# 404_Schematic.net
KiCad netlist of a schematic drawn in Altium Designer
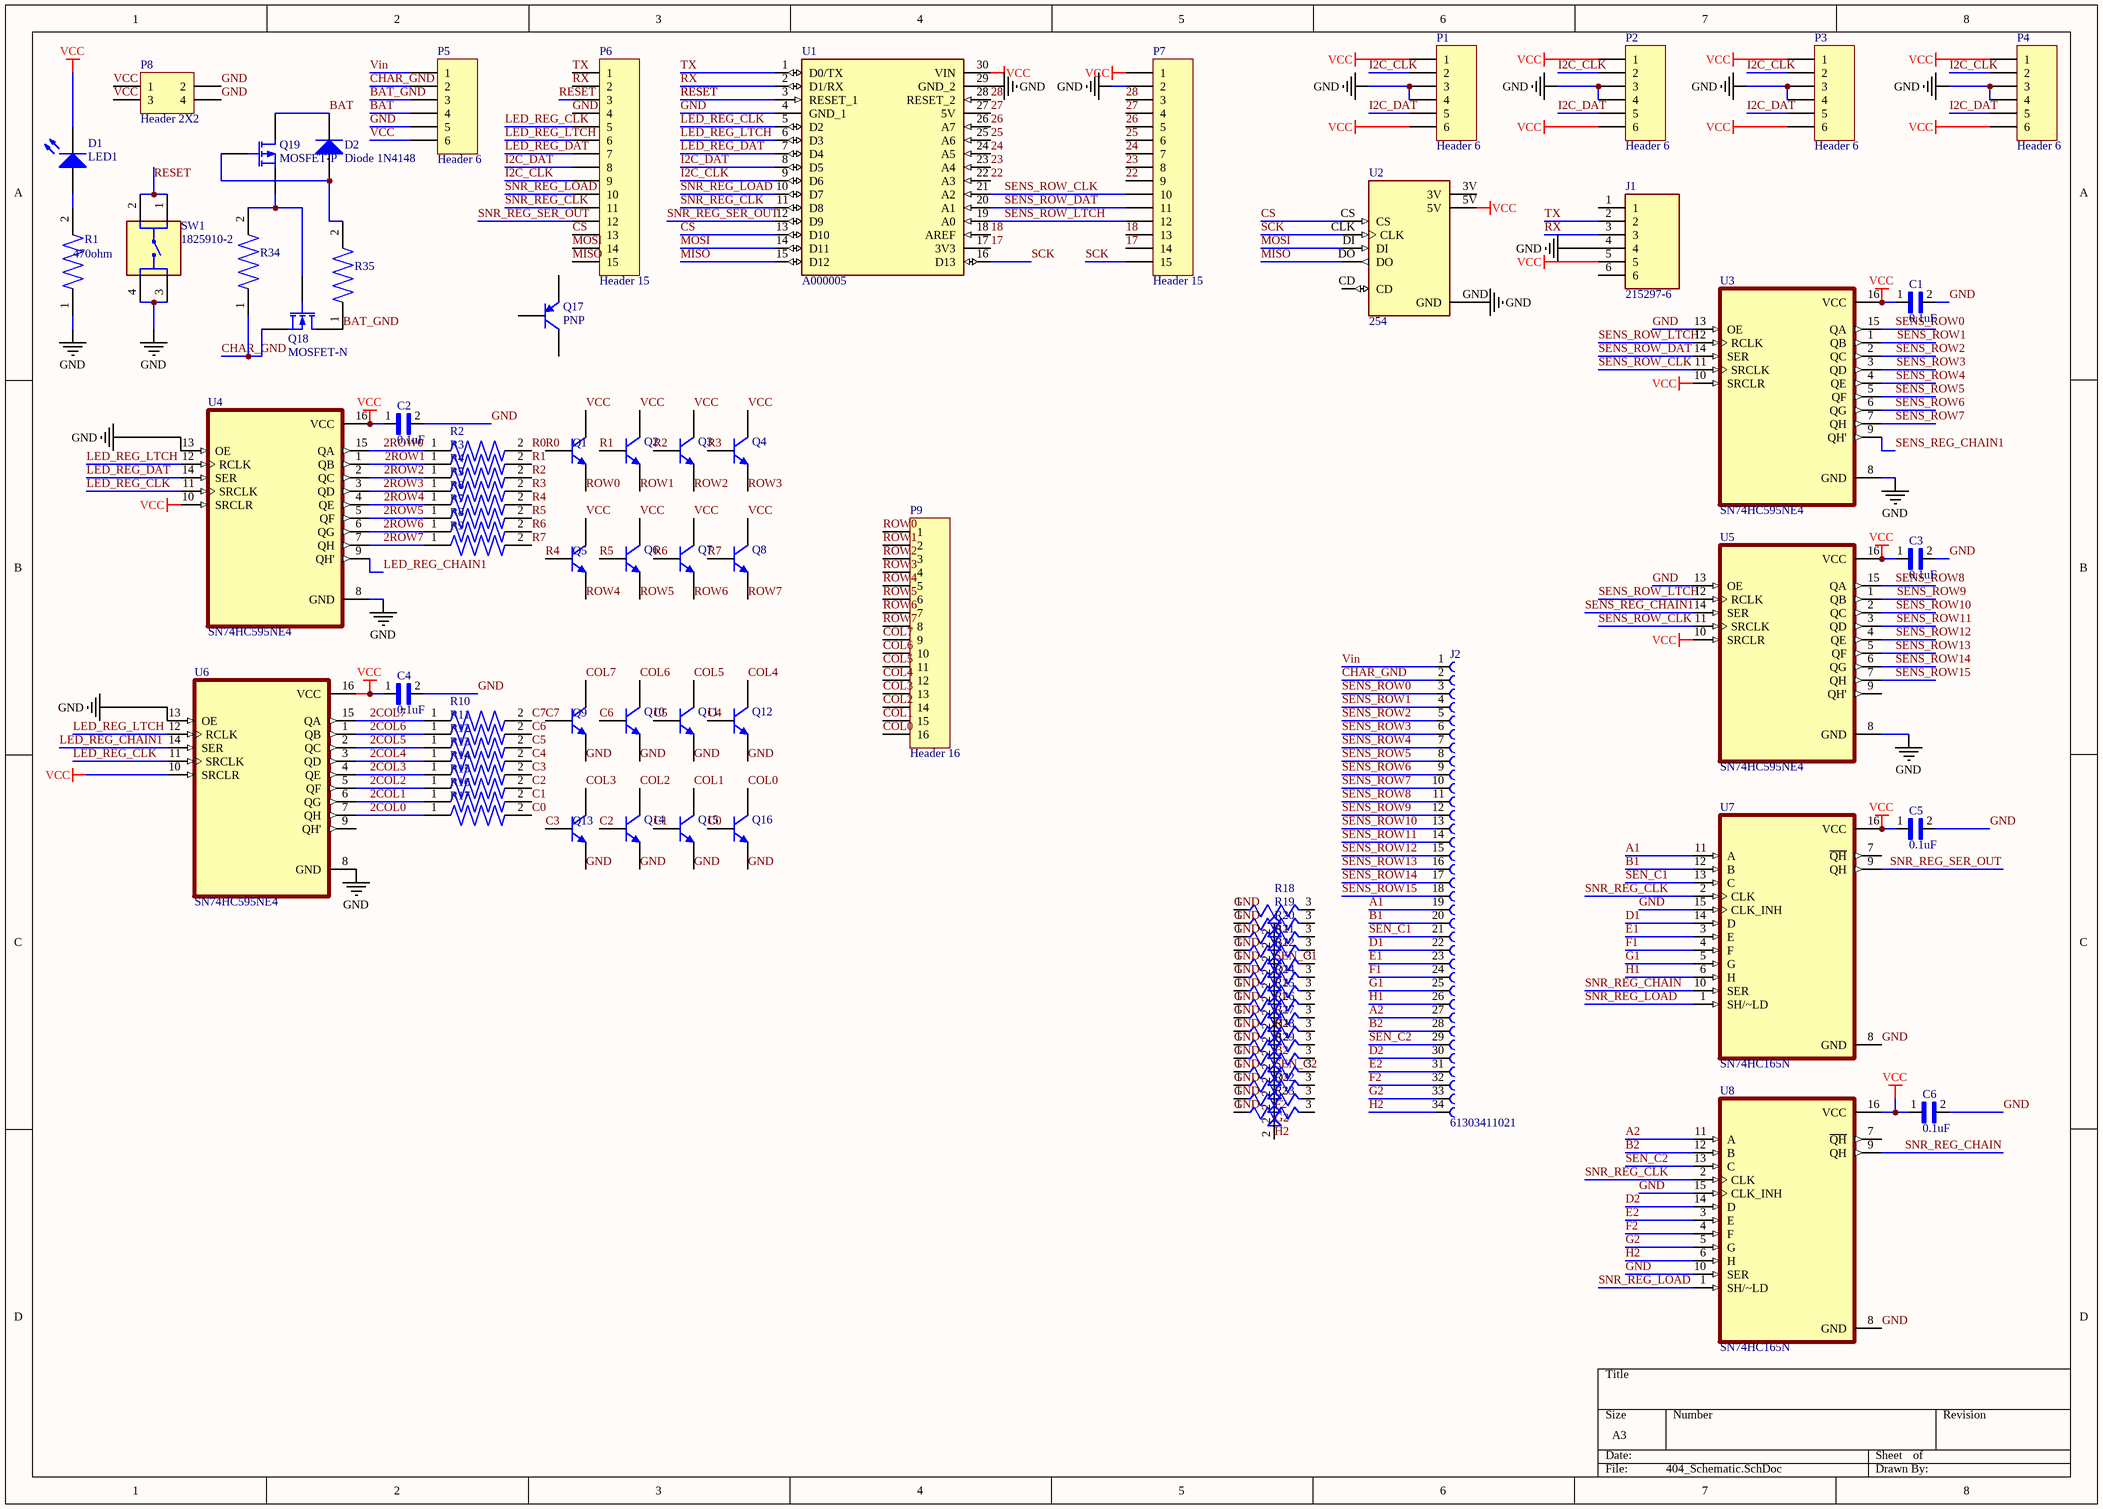
[diagram p0: 404_Schematic.SchDoc]

(export (version "E")
  (design (tool "Eeschema 10.0.6"))
  (components
    (comp (ref "C1")
      (value "0.1uF")
      (footprint "CAP_RDER72H103K1K1H03B")
      (description "Cap Ceramic 0.0047uF 50V C0G 5% Radial 5mm 125C Bulk")
      (fields (field (name "MP") "RDER72H103K1K1H03B") (field (name "MF") "{'manufacturer': u'Murata'}"))
      (libsource (lib "SnapEDA_Library") (part "RDER72H103K1K1H03B"))
    )
    (comp (ref "C2")
      (value "0.1uF")
      (footprint "CAP_RDER72H103K1K1H03B")
      (description "Cap Ceramic 0.0047uF 50V C0G 5% Radial 5mm 125C Bulk")
      (fields (field (name "MP") "RDER72H103K1K1H03B") (field (name "MF") "{'manufacturer': u'Murata'}"))
      (libsource (lib "SnapEDA_Library") (part "RDER72H103K1K1H03B"))
    )
    (comp (ref "C3")
      (value "0.1uF")
      (footprint "CAP_RDER72H103K1K1H03B")
      (description "Cap Ceramic 0.0047uF 50V C0G 5% Radial 5mm 125C Bulk")
      (fields (field (name "MP") "RDER72H103K1K1H03B") (field (name "MF") "{'manufacturer': u'Murata'}"))
      (libsource (lib "SnapEDA_Library") (part "RDER72H103K1K1H03B"))
    )
    (comp (ref "C4")
      (value "0.1uF")
      (footprint "CAP_RDER72H103K1K1H03B")
      (description "Cap Ceramic 0.0047uF 50V C0G 5% Radial 5mm 125C Bulk")
      (fields (field (name "MP") "RDER72H103K1K1H03B") (field (name "MF") "{'manufacturer': u'Murata'}"))
      (libsource (lib "SnapEDA_Library") (part "RDER72H103K1K1H03B"))
    )
    (comp (ref "C5")
      (value "0.1uF")
      (footprint "CAP_RDER72H103K1K1H03B")
      (description "Cap Ceramic 0.0047uF 50V C0G 5% Radial 5mm 125C Bulk")
      (fields (field (name "MP") "RDER72H103K1K1H03B") (field (name "MF") "{'manufacturer': u'Murata'}"))
      (libsource (lib "SnapEDA_Library") (part "RDER72H103K1K1H03B"))
    )
    (comp (ref "C6")
      (value "0.1uF")
      (footprint "CAP_RDER72H103K1K1H03B")
      (description "Cap Ceramic 0.0047uF 50V C0G 5% Radial 5mm 125C Bulk")
      (fields (field (name "MP") "RDER72H103K1K1H03B") (field (name "MF") "{'manufacturer': u'Murata'}"))
      (libsource (lib "SnapEDA_Library") (part "RDER72H103K1K1H03B"))
    )
    (comp (ref "D1")
      (value "LED1")
      (footprint "LED-1")
      (description "Typical RED GaAs LED")
      (fields (field (name "PUBLISHER") "Altium Limited"))
      (libsource (lib "Miscellaneous Devices") (part "LED1"))
    )
    (comp (ref "D2")
      (value "Diode 1N4148")
      (footprint "DO-35")
      (description "High Conductance Fast Diode")
      (fields (field (name "PUBLISHER") "Altium Limited"))
      (libsource (lib "Miscellaneous Devices") (part "Diode 1N4148"))
    )
    (comp (ref "J1")
      (value "215297-6")
      (footprint "TE_215297-6")
      (fields (field (name "MF") "{'manufacturer': u'TE Connectivity'}"))
      (libsource (lib "SnapEDA_Library") (part "215297-6"))
    )
    (comp (ref "J2")
      (value "61303411021")
      (footprint "61303411021:61303411021")
      (fields (field (name "MF") "{'manufacturer': u'~{W}xfcrth Elektronik'}"))
      (libsource (lib "*") (part "61303411021"))
    )
    (comp (ref "P1")
      (value "Header 6")
      (footprint "HDR1X6")
      (description "Header, 6-Pin")
      (fields (field (name "PUBLISHER") "Altium Limited"))
      (libsource (lib "Miscellaneous Connectors") (part "Header 6"))
    )
    (comp (ref "P2")
      (value "Header 6")
      (footprint "HDR1X6")
      (description "Header, 6-Pin")
      (fields (field (name "PUBLISHER") "Altium Limited"))
      (libsource (lib "Miscellaneous Connectors") (part "Header 6"))
    )
    (comp (ref "P3")
      (value "Header 6")
      (footprint "HDR1X6")
      (description "Header, 6-Pin")
      (fields (field (name "PUBLISHER") "Altium Limited"))
      (libsource (lib "Miscellaneous Connectors") (part "Header 6"))
    )
    (comp (ref "P4")
      (value "Header 6")
      (footprint "HDR1X6")
      (description "Header, 6-Pin")
      (fields (field (name "PUBLISHER") "Altium Limited"))
      (libsource (lib "Miscellaneous Connectors") (part "Header 6"))
    )
    (comp (ref "P5")
      (value "Header 6")
      (footprint "HDR1X6")
      (description "Header, 6-Pin")
      (fields (field (name "PUBLISHER") "Altium Limited"))
      (libsource (lib "Miscellaneous Connectors") (part "Header 6"))
    )
    (comp (ref "P6")
      (value "Header 15")
      (footprint "HDR1X15")
      (description "Header, 15-Pin")
      (fields (field (name "PUBLISHER") "Altium Limited"))
      (libsource (lib "Miscellaneous Connectors") (part "Header 15"))
    )
    (comp (ref "P7")
      (value "Header 15")
      (footprint "HDR1X15")
      (description "Header, 15-Pin")
      (fields (field (name "PUBLISHER") "Altium Limited"))
      (libsource (lib "Miscellaneous Connectors") (part "Header 15"))
    )
    (comp (ref "P8")
      (value "Header 2X2")
      (footprint "HDR2X2")
      (description "Header, 2-Pin, Dual row")
      (fields (field (name "PUBLISHER") "Altium Limited"))
      (libsource (lib "Miscellaneous Connectors") (part "Header 2X2"))
    )
    (comp (ref "P9")
      (value "Header 16")
      (footprint "HDR1X16")
      (description "Header, 16-Pin")
      (fields (field (name "PUBLISHER") "Altium Limited"))
      (libsource (lib "Miscellaneous Connectors") (part "Header 16"))
    )
    (comp (ref "Q1")
      (value "2N3904")
      (footprint "TO-92A")
      (description "NPN General Purpose Amplifier")
      (fields (field (name "PUBLISHER") "Altium Limited"))
      (libsource (lib "Miscellaneous Devices") (part "2N3904"))
    )
    (comp (ref "Q2")
      (value "2N3904")
      (footprint "TO-92A")
      (description "NPN General Purpose Amplifier")
      (fields (field (name "PUBLISHER") "Altium Limited"))
      (libsource (lib "Miscellaneous Devices") (part "2N3904"))
    )
    (comp (ref "Q3")
      (value "2N3904")
      (footprint "TO-92A")
      (description "NPN General Purpose Amplifier")
      (fields (field (name "PUBLISHER") "Altium Limited"))
      (libsource (lib "Miscellaneous Devices") (part "2N3904"))
    )
    (comp (ref "Q4")
      (value "2N3904")
      (footprint "TO-92A")
      (description "NPN General Purpose Amplifier")
      (fields (field (name "PUBLISHER") "Altium Limited"))
      (libsource (lib "Miscellaneous Devices") (part "2N3904"))
    )
    (comp (ref "Q5")
      (value "2N3904")
      (footprint "TO-92A")
      (description "NPN General Purpose Amplifier")
      (fields (field (name "PUBLISHER") "Altium Limited"))
      (libsource (lib "Miscellaneous Devices") (part "2N3904"))
    )
    (comp (ref "Q6")
      (value "2N3904")
      (footprint "TO-92A")
      (description "NPN General Purpose Amplifier")
      (fields (field (name "PUBLISHER") "Altium Limited"))
      (libsource (lib "Miscellaneous Devices") (part "2N3904"))
    )
    (comp (ref "Q7")
      (value "2N3904")
      (footprint "TO-92A")
      (description "NPN General Purpose Amplifier")
      (fields (field (name "PUBLISHER") "Altium Limited"))
      (libsource (lib "Miscellaneous Devices") (part "2N3904"))
    )
    (comp (ref "Q8")
      (value "2N3904")
      (footprint "TO-92A")
      (description "NPN General Purpose Amplifier")
      (fields (field (name "PUBLISHER") "Altium Limited"))
      (libsource (lib "Miscellaneous Devices") (part "2N3904"))
    )
    (comp (ref "Q9")
      (value "2N3904")
      (footprint "TO-92A")
      (description "NPN General Purpose Amplifier")
      (fields (field (name "PUBLISHER") "Altium Limited"))
      (libsource (lib "Miscellaneous Devices") (part "2N3904"))
    )
    (comp (ref "Q10")
      (value "2N3904")
      (footprint "TO-92A")
      (description "NPN General Purpose Amplifier")
      (fields (field (name "PUBLISHER") "Altium Limited"))
      (libsource (lib "Miscellaneous Devices") (part "2N3904"))
    )
    (comp (ref "Q11")
      (value "2N3904")
      (footprint "TO-92A")
      (description "NPN General Purpose Amplifier")
      (fields (field (name "PUBLISHER") "Altium Limited"))
      (libsource (lib "Miscellaneous Devices") (part "2N3904"))
    )
    (comp (ref "Q12")
      (value "2N3904")
      (footprint "TO-92A")
      (description "NPN General Purpose Amplifier")
      (fields (field (name "PUBLISHER") "Altium Limited"))
      (libsource (lib "Miscellaneous Devices") (part "2N3904"))
    )
    (comp (ref "Q13")
      (value "2N3904")
      (footprint "TO-92A")
      (description "NPN General Purpose Amplifier")
      (fields (field (name "PUBLISHER") "Altium Limited"))
      (libsource (lib "Miscellaneous Devices") (part "2N3904"))
    )
    (comp (ref "Q14")
      (value "2N3904")
      (footprint "TO-92A")
      (description "NPN General Purpose Amplifier")
      (fields (field (name "PUBLISHER") "Altium Limited"))
      (libsource (lib "Miscellaneous Devices") (part "2N3904"))
    )
    (comp (ref "Q15")
      (value "2N3904")
      (footprint "TO-92A")
      (description "NPN General Purpose Amplifier")
      (fields (field (name "PUBLISHER") "Altium Limited"))
      (libsource (lib "Miscellaneous Devices") (part "2N3904"))
    )
    (comp (ref "Q16")
      (value "2N3904")
      (footprint "TO-92A")
      (description "NPN General Purpose Amplifier")
      (fields (field (name "PUBLISHER") "Altium Limited"))
      (libsource (lib "Miscellaneous Devices") (part "2N3904"))
    )
    (comp (ref "Q17")
      (value "PNP")
      (footprint "SOT-23B_N")
      (description "PNP Bipolar Transistor")
      (fields (field (name "PUBLISHER") "Altium Limited"))
      (libsource (lib "Miscellaneous Devices") (part "PNP"))
    )
    (comp (ref "Q18")
      (value "MOSFET-N")
      (footprint "E3")
      (description "N-Channel MOSFET")
      (fields (field (name "PUBLISHER") "Altium Limited"))
      (libsource (lib "Miscellaneous Devices") (part "MOSFET-N"))
    )
    (comp (ref "Q19")
      (value "MOSFET-P")
      (footprint "E3")
      (description "P-Channel MOSFET")
      (fields (field (name "PUBLISHER") "Altium Limited"))
      (libsource (lib "Miscellaneous Devices") (part "MOSFET-P"))
    )
    (comp (ref "R1")
      (value "470ohm")
      (footprint "2-1623928-5:RESAD700W45L350D185")
      (description "CFR16 5% 10K 470 ohm")
      (fields (field (name "MP") "2-1623928-5") (field (name "MF") "{'manufacturer': u'TE Connectivity'}"))
      (libsource (lib "*") (part "2-1623928-5"))
    )
    (comp (ref "R2")
      (value "390")
      (footprint "RESAD700W45L350D185")
      (description "CFR16 5% 10K")
      (fields (field (name "MF") "{'manufacturer': u'TE Connectivity'}") (field (name "MP") "1-1623928-1"))
      (libsource (lib "SnapEDA_Library") (part "1-1623928-1"))
    )
    (comp (ref "R3")
      (value "390")
      (footprint "RESAD700W45L350D185")
      (description "CFR16 5% 10K")
      (fields (field (name "MF") "{'manufacturer': u'TE Connectivity'}") (field (name "MP") "1-1623928-1"))
      (libsource (lib "SnapEDA_Library") (part "1-1623928-1"))
    )
    (comp (ref "R4")
      (value "390")
      (footprint "RESAD700W45L350D185")
      (description "CFR16 5% 10K")
      (fields (field (name "MF") "{'manufacturer': u'TE Connectivity'}") (field (name "MP") "1-1623928-1"))
      (libsource (lib "SnapEDA_Library") (part "1-1623928-1"))
    )
    (comp (ref "R5")
      (value "~")
      (footprint "RESAD700W45L350D185")
      (description "CFR16 5% 10K")
      (fields (field (name "MF") "{'manufacturer': u'TE Connectivity'}") (field (name "MP") "1-1623928-1"))
      (libsource (lib "SnapEDA_Library") (part "1-1623928-1"))
    )
    (comp (ref "R6")
      (value "1-1623928-1")
      (footprint "RESAD700W45L350D185")
      (description "CFR16 5% 10K")
      (fields (field (name "MF") "{'manufacturer': u'TE Connectivity'}"))
      (libsource (lib "SnapEDA_Library") (part "1-1623928-1"))
    )
    (comp (ref "R7")
      (value "1-1623928-1")
      (footprint "RESAD700W45L350D185")
      (description "CFR16 5% 10K")
      (fields (field (name "MF") "{'manufacturer': u'TE Connectivity'}"))
      (libsource (lib "SnapEDA_Library") (part "1-1623928-1"))
    )
    (comp (ref "R8")
      (value "1-1623928-1")
      (footprint "RESAD700W45L350D185")
      (description "CFR16 5% 10K")
      (fields (field (name "MF") "{'manufacturer': u'TE Connectivity'}"))
      (libsource (lib "SnapEDA_Library") (part "1-1623928-1"))
    )
    (comp (ref "R9")
      (value "1-1623928-1")
      (footprint "RESAD700W45L350D185")
      (description "CFR16 5% 10K")
      (fields (field (name "MF") "{'manufacturer': u'TE Connectivity'}"))
      (libsource (lib "SnapEDA_Library") (part "1-1623928-1"))
    )
    (comp (ref "R10")
      (value "390")
      (footprint "RESAD700W45L350D185")
      (description "CFR16 5% 10K")
      (fields (field (name "MF") "{'manufacturer': u'TE Connectivity'}") (field (name "MP") "1-1623928-1"))
      (libsource (lib "SnapEDA_Library") (part "1-1623928-1"))
    )
    (comp (ref "R11")
      (value "390")
      (footprint "RESAD700W45L350D185")
      (description "CFR16 5% 10K")
      (fields (field (name "MF") "{'manufacturer': u'TE Connectivity'}") (field (name "MP") "1-1623928-1"))
      (libsource (lib "SnapEDA_Library") (part "1-1623928-1"))
    )
    (comp (ref "R12")
      (value "390")
      (footprint "RESAD700W45L350D185")
      (description "CFR16 5% 10K")
      (fields (field (name "MF") "{'manufacturer': u'TE Connectivity'}") (field (name "MP") "1-1623928-1"))
      (libsource (lib "SnapEDA_Library") (part "1-1623928-1"))
    )
    (comp (ref "R13")
      (value "~")
      (footprint "RESAD700W45L350D185")
      (description "CFR16 5% 10K")
      (fields (field (name "MF") "{'manufacturer': u'TE Connectivity'}") (field (name "MP") "1-1623928-1"))
      (libsource (lib "SnapEDA_Library") (part "1-1623928-1"))
    )
    (comp (ref "R14")
      (value "1-1623928-1")
      (footprint "RESAD700W45L350D185")
      (description "CFR16 5% 10K")
      (fields (field (name "MF") "{'manufacturer': u'TE Connectivity'}"))
      (libsource (lib "SnapEDA_Library") (part "1-1623928-1"))
    )
    (comp (ref "R15")
      (value "1-1623928-1")
      (footprint "RESAD700W45L350D185")
      (description "CFR16 5% 10K")
      (fields (field (name "MF") "{'manufacturer': u'TE Connectivity'}"))
      (libsource (lib "SnapEDA_Library") (part "1-1623928-1"))
    )
    (comp (ref "R16")
      (value "1-1623928-1")
      (footprint "RESAD700W45L350D185")
      (description "CFR16 5% 10K")
      (fields (field (name "MF") "{'manufacturer': u'TE Connectivity'}"))
      (libsource (lib "SnapEDA_Library") (part "1-1623928-1"))
    )
    (comp (ref "R17")
      (value "1-1623928-1")
      (footprint "RESAD700W45L350D185")
      (description "CFR16 5% 10K")
      (fields (field (name "MF") "{'manufacturer': u'TE Connectivity'}"))
      (libsource (lib "SnapEDA_Library") (part "1-1623928-1"))
    )
    (comp (ref "R18")
      (value "3352T-1-103LF")
      (footprint "3352T-1-103LF:TRIM_3352T-1-103LF")
      (description "10 kOhms 0.5W, 1/2W Through Hole Thumbwheel Potentiometer Top Adjustment")
      (fields (field (name "MF") "{'manufacturer': u'Bourns'}"))
      (libsource (lib "*") (part "3352T-1-103LF"))
    )
    (comp (ref "R19")
      (value "3352T-1-103LF")
      (footprint "3352T-1-103LF:TRIM_3352T-1-103LF")
      (description "10 kOhms 0.5W, 1/2W Through Hole Thumbwheel Potentiometer Top Adjustment")
      (fields (field (name "MF") "{'manufacturer': u'Bourns'}"))
      (libsource (lib "*") (part "3352T-1-103LF"))
    )
    (comp (ref "R20")
      (value "3352T-1-103LF")
      (footprint "3352T-1-103LF:TRIM_3352T-1-103LF")
      (description "10 kOhms 0.5W, 1/2W Through Hole Thumbwheel Potentiometer Top Adjustment")
      (fields (field (name "MF") "{'manufacturer': u'Bourns'}"))
      (libsource (lib "*") (part "3352T-1-103LF"))
    )
    (comp (ref "R21")
      (value "3352T-1-103LF")
      (footprint "3352T-1-103LF:TRIM_3352T-1-103LF")
      (description "10 kOhms 0.5W, 1/2W Through Hole Thumbwheel Potentiometer Top Adjustment")
      (fields (field (name "MF") "{'manufacturer': u'Bourns'}"))
      (libsource (lib "*") (part "3352T-1-103LF"))
    )
    (comp (ref "R22")
      (value "3352T-1-103LF")
      (footprint "3352T-1-103LF:TRIM_3352T-1-103LF")
      (description "10 kOhms 0.5W, 1/2W Through Hole Thumbwheel Potentiometer Top Adjustment")
      (fields (field (name "MF") "{'manufacturer': u'Bourns'}"))
      (libsource (lib "*") (part "3352T-1-103LF"))
    )
    (comp (ref "R23")
      (value "3352T-1-103LF")
      (footprint "3352T-1-103LF:TRIM_3352T-1-103LF")
      (description "10 kOhms 0.5W, 1/2W Through Hole Thumbwheel Potentiometer Top Adjustment")
      (fields (field (name "MF") "{'manufacturer': u'Bourns'}"))
      (libsource (lib "*") (part "3352T-1-103LF"))
    )
    (comp (ref "R24")
      (value "3352T-1-103LF")
      (footprint "3352T-1-103LF:TRIM_3352T-1-103LF")
      (description "10 kOhms 0.5W, 1/2W Through Hole Thumbwheel Potentiometer Top Adjustment")
      (fields (field (name "MF") "{'manufacturer': u'Bourns'}"))
      (libsource (lib "*") (part "3352T-1-103LF"))
    )
    (comp (ref "R25")
      (value "3352T-1-103LF")
      (footprint "3352T-1-103LF:TRIM_3352T-1-103LF")
      (description "10 kOhms 0.5W, 1/2W Through Hole Thumbwheel Potentiometer Top Adjustment")
      (fields (field (name "MF") "{'manufacturer': u'Bourns'}"))
      (libsource (lib "*") (part "3352T-1-103LF"))
    )
    (comp (ref "R26")
      (value "3352T-1-103LF")
      (footprint "3352T-1-103LF:TRIM_3352T-1-103LF")
      (description "10 kOhms 0.5W, 1/2W Through Hole Thumbwheel Potentiometer Top Adjustment")
      (fields (field (name "MF") "{'manufacturer': u'Bourns'}"))
      (libsource (lib "*") (part "3352T-1-103LF"))
    )
    (comp (ref "R27")
      (value "3352T-1-103LF")
      (footprint "3352T-1-103LF:TRIM_3352T-1-103LF")
      (description "10 kOhms 0.5W, 1/2W Through Hole Thumbwheel Potentiometer Top Adjustment")
      (fields (field (name "MF") "{'manufacturer': u'Bourns'}"))
      (libsource (lib "*") (part "3352T-1-103LF"))
    )
    (comp (ref "R28")
      (value "3352T-1-103LF")
      (footprint "3352T-1-103LF:TRIM_3352T-1-103LF")
      (description "10 kOhms 0.5W, 1/2W Through Hole Thumbwheel Potentiometer Top Adjustment")
      (fields (field (name "MF") "{'manufacturer': u'Bourns'}"))
      (libsource (lib "*") (part "3352T-1-103LF"))
    )
    (comp (ref "R29")
      (value "3352T-1-103LF")
      (footprint "3352T-1-103LF:TRIM_3352T-1-103LF")
      (description "10 kOhms 0.5W, 1/2W Through Hole Thumbwheel Potentiometer Top Adjustment")
      (fields (field (name "MF") "{'manufacturer': u'Bourns'}"))
      (libsource (lib "*") (part "3352T-1-103LF"))
    )
    (comp (ref "R30")
      (value "3352T-1-103LF")
      (footprint "3352T-1-103LF:TRIM_3352T-1-103LF")
      (description "10 kOhms 0.5W, 1/2W Through Hole Thumbwheel Potentiometer Top Adjustment")
      (fields (field (name "MF") "{'manufacturer': u'Bourns'}"))
      (libsource (lib "*") (part "3352T-1-103LF"))
    )
    (comp (ref "R31")
      (value "3352T-1-103LF")
      (footprint "3352T-1-103LF:TRIM_3352T-1-103LF")
      (description "10 kOhms 0.5W, 1/2W Through Hole Thumbwheel Potentiometer Top Adjustment")
      (fields (field (name "MF") "{'manufacturer': u'Bourns'}"))
      (libsource (lib "*") (part "3352T-1-103LF"))
    )
    (comp (ref "R32")
      (value "3352T-1-103LF")
      (footprint "3352T-1-103LF:TRIM_3352T-1-103LF")
      (description "10 kOhms 0.5W, 1/2W Through Hole Thumbwheel Potentiometer Top Adjustment")
      (fields (field (name "MF") "{'manufacturer': u'Bourns'}"))
      (libsource (lib "*") (part "3352T-1-103LF"))
    )
    (comp (ref "R33")
      (value "3352T-1-103LF")
      (footprint "3352T-1-103LF:TRIM_3352T-1-103LF")
      (description "10 kOhms 0.5W, 1/2W Through Hole Thumbwheel Potentiometer Top Adjustment")
      (fields (field (name "MF") "{'manufacturer': u'Bourns'}"))
      (libsource (lib "*") (part "3352T-1-103LF"))
    )
    (comp (ref "R34")
      (value "390")
      (footprint "RESAD700W45L350D185")
      (description "CFR16 5% 10K")
      (fields (field (name "MF") "{'manufacturer': u'TE Connectivity'}") (field (name "MP") "1-1623928-1"))
      (libsource (lib "SnapEDA_Library") (part "1-1623928-1"))
    )
    (comp (ref "R35")
      (value "390")
      (footprint "RESAD700W45L350D185")
      (description "CFR16 5% 10K")
      (fields (field (name "MF") "{'manufacturer': u'TE Connectivity'}") (field (name "MP") "1-1623928-1"))
      (libsource (lib "SnapEDA_Library") (part "1-1623928-1"))
    )
    (comp (ref "SW1")
      (value "1825910-2")
      (footprint "1825910-2:TE_1825910-2")
      (description "SWITCH TACTILE SPST-NO 0.05A 24V")
      (fields (field (name "MF") "{'manufacturer': u'TE Connectivity'}"))
      (libsource (lib "*") (part "1825910-2"))
    )
    (comp (ref "U1")
      (value "A000005")
      (footprint "A000005:MODULE_A000005")
      (description "CLOCK SAW OSCILLATOR SEAM7050 T&")
      (fields (field (name "MF") "{'manufacturer': u'Arduino'}"))
      (libsource (lib "*") (part "A000005"))
    )
    (comp (ref "U2")
      (value "254")
      (footprint "254:MODULE_254")
      (description "MICROSD CARD BREAKOUT 5V OR 3V")
      (fields (field (name "MF") "{'manufacturer': u'Adafruit'}"))
      (libsource (lib "*") (part "254"))
    )
    (comp (ref "U3")
      (value "SN74HC595NE4")
      (footprint "DIP794W45P254L1969H508Q16")
      (fields (field (name "MF") "{'manufacturer': u'Texas Instruments'}"))
      (libsource (lib "404Library") (part "SN74HC595NE4"))
    )
    (comp (ref "U4")
      (value "SN74HC595NE4")
      (footprint "DIP794W45P254L1969H508Q16")
      (fields (field (name "MF") "{'manufacturer': u'Texas Instruments'}"))
      (libsource (lib "404Library") (part "SN74HC595NE4"))
    )
    (comp (ref "U5")
      (value "SN74HC595NE4")
      (footprint "DIP794W45P254L1969H508Q16")
      (fields (field (name "MF") "{'manufacturer': u'Texas Instruments'}"))
      (libsource (lib "404Library") (part "SN74HC595NE4"))
    )
    (comp (ref "U6")
      (value "SN74HC595NE4")
      (footprint "DIP794W45P254L1969H508Q16")
      (fields (field (name "MF") "{'manufacturer': u'Texas Instruments'}"))
      (libsource (lib "404Library") (part "SN74HC595NE4"))
    )
    (comp (ref "U7")
      (value "SN74HC165N")
      (footprint "DIP794W45P254L1969H508Q16")
      (fields (field (name "MF") "{'manufacturer': u'Texas Instruments'}"))
      (libsource (lib "404Library") (part "SN74HC165N"))
    )
    (comp (ref "U8")
      (value "SN74HC165N")
      (footprint "DIP794W45P254L1969H508Q16")
      (fields (field (name "MF") "{'manufacturer': u'Texas Instruments'}"))
      (libsource (lib "404Library") (part "SN74HC165N"))
    )
  )
  (nets
    (net (code "1") (name "/2COL0") (class "Default")
      (node (ref "R17") (pin "1") (pinfunction "1_1") (pintype "passive"))
      (node (ref "U6") (pin "7") (pinfunction "QH_7") (pintype "output"))
    )
    (net (code "2") (name "/2COL1") (class "Default")
      (node (ref "R16") (pin "1") (pinfunction "1_1") (pintype "passive"))
      (node (ref "U6") (pin "6") (pinfunction "QG_6") (pintype "output"))
    )
    (net (code "3") (name "/2COL2") (class "Default")
      (node (ref "R15") (pin "1") (pinfunction "1_1") (pintype "passive"))
      (node (ref "U6") (pin "5") (pinfunction "QF_5") (pintype "output"))
    )
    (net (code "4") (name "/2COL3") (class "Default")
      (node (ref "R14") (pin "1") (pinfunction "1_1") (pintype "passive"))
      (node (ref "U6") (pin "4") (pinfunction "QE_4") (pintype "output"))
    )
    (net (code "5") (name "/2COL4") (class "Default")
      (node (ref "R13") (pin "1") (pinfunction "1_1") (pintype "passive"))
      (node (ref "U6") (pin "3") (pinfunction "QD_3") (pintype "output"))
    )
    (net (code "6") (name "/2COL5") (class "Default")
      (node (ref "R12") (pin "1") (pinfunction "1_1") (pintype "passive"))
      (node (ref "U6") (pin "2") (pinfunction "QC_2") (pintype "output"))
    )
    (net (code "7") (name "/2COL6") (class "Default")
      (node (ref "R11") (pin "1") (pinfunction "1_1") (pintype "passive"))
      (node (ref "U6") (pin "1") (pinfunction "QB_1") (pintype "output"))
    )
    (net (code "8") (name "/2COL7") (class "Default")
      (node (ref "R10") (pin "1") (pinfunction "1_1") (pintype "passive"))
      (node (ref "U6") (pin "15") (pinfunction "QA_15") (pintype "output"))
    )
    (net (code "9") (name "/2ROW0") (class "Default")
      (node (ref "R2") (pin "1") (pinfunction "1_1") (pintype "passive"))
      (node (ref "U4") (pin "15") (pinfunction "QA_15") (pintype "output"))
    )
    (net (code "10") (name "/2ROW1") (class "Default")
      (node (ref "R3") (pin "1") (pinfunction "1_1") (pintype "passive"))
      (node (ref "U4") (pin "1") (pinfunction "QB_1") (pintype "output"))
    )
    (net (code "11") (name "/2ROW2") (class "Default")
      (node (ref "R4") (pin "1") (pinfunction "1_1") (pintype "passive"))
      (node (ref "U4") (pin "2") (pinfunction "QC_2") (pintype "output"))
    )
    (net (code "12") (name "/2ROW3") (class "Default")
      (node (ref "R5") (pin "1") (pinfunction "1_1") (pintype "passive"))
      (node (ref "U4") (pin "3") (pinfunction "QD_3") (pintype "output"))
    )
    (net (code "13") (name "/2ROW4") (class "Default")
      (node (ref "R6") (pin "1") (pinfunction "1_1") (pintype "passive"))
      (node (ref "U4") (pin "4") (pinfunction "QE_4") (pintype "output"))
    )
    (net (code "14") (name "/2ROW5") (class "Default")
      (node (ref "R7") (pin "1") (pinfunction "1_1") (pintype "passive"))
      (node (ref "U4") (pin "5") (pinfunction "QF_5") (pintype "output"))
    )
    (net (code "15") (name "/2ROW6") (class "Default")
      (node (ref "R8") (pin "1") (pinfunction "1_1") (pintype "passive"))
      (node (ref "U4") (pin "6") (pinfunction "QG_6") (pintype "output"))
    )
    (net (code "16") (name "/2ROW7") (class "Default")
      (node (ref "R9") (pin "1") (pinfunction "1_1") (pintype "passive"))
      (node (ref "U4") (pin "7") (pinfunction "QH_7") (pintype "output"))
    )
    (net (code "17") (name "/17") (class "Default")
      (node (ref "P7") (pin "14") (pinfunction "14_14") (pintype "passive"))
      (node (ref "U1") (pin "17") (pinfunction "3V3_17") (pintype "power_in"))
    )
    (net (code "18") (name "/18") (class "Default")
      (node (ref "P7") (pin "13") (pinfunction "13_13") (pintype "passive"))
      (node (ref "U1") (pin "18") (pinfunction "AREF_18") (pintype "input"))
    )
    (net (code "19") (name "/22") (class "Default")
      (node (ref "P7") (pin "9") (pinfunction "9_9") (pintype "passive"))
      (node (ref "U1") (pin "22") (pinfunction "A3_22") (pintype "input"))
    )
    (net (code "20") (name "/23") (class "Default")
      (node (ref "P7") (pin "8") (pinfunction "8_8") (pintype "passive"))
      (node (ref "U1") (pin "23") (pinfunction "A4_23") (pintype "input"))
    )
    (net (code "21") (name "/24") (class "Default")
      (node (ref "P7") (pin "7") (pinfunction "7_7") (pintype "passive"))
      (node (ref "U1") (pin "24") (pinfunction "A5_24") (pintype "input"))
    )
    (net (code "22") (name "/25") (class "Default")
      (node (ref "P7") (pin "6") (pinfunction "6_6") (pintype "passive"))
      (node (ref "U1") (pin "25") (pinfunction "A6_25") (pintype "input"))
    )
    (net (code "23") (name "/26") (class "Default")
      (node (ref "P7") (pin "5") (pinfunction "5_5") (pintype "passive"))
      (node (ref "U1") (pin "26") (pinfunction "A7_26") (pintype "input"))
    )
    (net (code "24") (name "/27") (class "Default")
      (node (ref "P7") (pin "4") (pinfunction "4_4") (pintype "passive"))
      (node (ref "U1") (pin "27") (pinfunction "5V_27") (pintype "power_in"))
    )
    (net (code "25") (name "/28") (class "Default")
      (node (ref "P7") (pin "3") (pinfunction "3_3") (pintype "passive"))
      (node (ref "U1") (pin "28") (pinfunction "RESET_2_28") (pintype "input"))
    )
    (net (code "26") (name "/A1") (class "Default")
      (node (ref "J2") (pin "19") (pinfunction "19_19") (pintype "passive"))
      (node (ref "R18") (pin "2") (pinfunction "WIPER_2") (pintype "passive"))
      (node (ref "U7") (pin "11") (pinfunction "A_11") (pintype "input"))
    )
    (net (code "27") (name "/A2") (class "Default")
      (node (ref "J2") (pin "27") (pinfunction "27_27") (pintype "passive"))
      (node (ref "R26") (pin "2") (pinfunction "WIPER_2") (pintype "passive"))
      (node (ref "U8") (pin "11") (pinfunction "A_11") (pintype "input"))
    )
    (net (code "28") (name "/B1") (class "Default")
      (node (ref "J2") (pin "20") (pinfunction "20_20") (pintype "passive"))
      (node (ref "R19") (pin "2") (pinfunction "WIPER_2") (pintype "passive"))
      (node (ref "U7") (pin "12") (pinfunction "B_12") (pintype "input"))
    )
    (net (code "29") (name "/B2") (class "Default")
      (node (ref "J2") (pin "28") (pinfunction "28_28") (pintype "passive"))
      (node (ref "R27") (pin "2") (pinfunction "WIPER_2") (pintype "passive"))
      (node (ref "U8") (pin "12") (pinfunction "B_12") (pintype "input"))
    )
    (net (code "30") (name "/BAT") (class "Default")
      (node (ref "D2") (pin "2") (pinfunction "K_2") (pintype "passive"))
      (node (ref "P5") (pin "4") (pinfunction "4_4") (pintype "passive"))
      (node (ref "Q19") (pin "1") (pinfunction "D_1") (pintype "passive"))
    )
    (net (code "31") (name "/BAT_GND") (class "Default")
      (node (ref "P5") (pin "3") (pinfunction "3_3") (pintype "passive"))
      (node (ref "Q18") (pin "1") (pinfunction "D_1") (pintype "passive"))
      (node (ref "R35") (pin "1") (pinfunction "1_1") (pintype "passive"))
    )
    (net (code "32") (name "/C0") (class "Default")
      (node (ref "Q16") (pin "2") (pinfunction "B_2") (pintype "passive"))
      (node (ref "R17") (pin "2") (pinfunction "2_2") (pintype "passive"))
    )
    (net (code "33") (name "/C1") (class "Default")
      (node (ref "Q15") (pin "2") (pinfunction "B_2") (pintype "passive"))
      (node (ref "R16") (pin "2") (pinfunction "2_2") (pintype "passive"))
    )
    (net (code "34") (name "/C2") (class "Default")
      (node (ref "Q14") (pin "2") (pinfunction "B_2") (pintype "passive"))
      (node (ref "R15") (pin "2") (pinfunction "2_2") (pintype "passive"))
    )
    (net (code "35") (name "/C3") (class "Default")
      (node (ref "Q13") (pin "2") (pinfunction "B_2") (pintype "passive"))
      (node (ref "R14") (pin "2") (pinfunction "2_2") (pintype "passive"))
    )
    (net (code "36") (name "/C4") (class "Default")
      (node (ref "Q12") (pin "2") (pinfunction "B_2") (pintype "passive"))
      (node (ref "R13") (pin "2") (pinfunction "2_2") (pintype "passive"))
    )
    (net (code "37") (name "/C5") (class "Default")
      (node (ref "Q11") (pin "2") (pinfunction "B_2") (pintype "passive"))
      (node (ref "R12") (pin "2") (pinfunction "2_2") (pintype "passive"))
    )
    (net (code "38") (name "/C6") (class "Default")
      (node (ref "Q10") (pin "2") (pinfunction "B_2") (pintype "passive"))
      (node (ref "R11") (pin "2") (pinfunction "2_2") (pintype "passive"))
    )
    (net (code "39") (name "/C7") (class "Default")
      (node (ref "Q9") (pin "2") (pinfunction "B_2") (pintype "passive"))
      (node (ref "R10") (pin "2") (pinfunction "2_2") (pintype "passive"))
    )
    (net (code "40") (name "/CHAR_GND") (class "Default")
      (node (ref "J2") (pin "2") (pinfunction "2_2") (pintype "passive"))
      (node (ref "P5") (pin "2") (pinfunction "2_2") (pintype "passive"))
      (node (ref "Q18") (pin "3") (pinfunction "S_3") (pintype "passive"))
      (node (ref "R34") (pin "1") (pinfunction "1_1") (pintype "passive"))
    )
    (net (code "41") (name "/COL0") (class "Default")
      (node (ref "P9") (pin "16") (pinfunction "16_16") (pintype "passive"))
      (node (ref "Q16") (pin "3") (pinfunction "C_3") (pintype "passive"))
    )
    (net (code "42") (name "/COL1") (class "Default")
      (node (ref "P9") (pin "15") (pinfunction "15_15") (pintype "passive"))
      (node (ref "Q15") (pin "3") (pinfunction "C_3") (pintype "passive"))
    )
    (net (code "43") (name "/COL2") (class "Default")
      (node (ref "P9") (pin "14") (pinfunction "14_14") (pintype "passive"))
      (node (ref "Q14") (pin "3") (pinfunction "C_3") (pintype "passive"))
    )
    (net (code "44") (name "/COL3") (class "Default")
      (node (ref "P9") (pin "13") (pinfunction "13_13") (pintype "passive"))
      (node (ref "Q13") (pin "3") (pinfunction "C_3") (pintype "passive"))
    )
    (net (code "45") (name "/COL4") (class "Default")
      (node (ref "P9") (pin "12") (pinfunction "12_12") (pintype "passive"))
      (node (ref "Q12") (pin "3") (pinfunction "C_3") (pintype "passive"))
    )
    (net (code "46") (name "/COL5") (class "Default")
      (node (ref "P9") (pin "11") (pinfunction "11_11") (pintype "passive"))
      (node (ref "Q11") (pin "3") (pinfunction "C_3") (pintype "passive"))
    )
    (net (code "47") (name "/COL6") (class "Default")
      (node (ref "P9") (pin "10") (pinfunction "10_10") (pintype "passive"))
      (node (ref "Q10") (pin "3") (pinfunction "C_3") (pintype "passive"))
    )
    (net (code "48") (name "/COL7") (class "Default")
      (node (ref "P9") (pin "9") (pinfunction "9_9") (pintype "passive"))
      (node (ref "Q9") (pin "3") (pinfunction "C_3") (pintype "passive"))
    )
    (net (code "49") (name "/CS") (class "Default")
      (node (ref "P6") (pin "13") (pinfunction "13_13") (pintype "passive"))
      (node (ref "U1") (pin "13") (pinfunction "D10_13") (pintype "bidirectional"))
      (node (ref "U2") (pin "CS") (pinfunction "CS_CS") (pintype "input"))
    )
    (net (code "50") (name "/D1") (class "Default")
      (node (ref "J2") (pin "22") (pinfunction "22_22") (pintype "passive"))
      (node (ref "R21") (pin "2") (pinfunction "WIPER_2") (pintype "passive"))
      (node (ref "U7") (pin "14") (pinfunction "D_14") (pintype "input"))
    )
    (net (code "51") (name "/D2") (class "Default")
      (node (ref "J2") (pin "30") (pinfunction "30_30") (pintype "passive"))
      (node (ref "R29") (pin "2") (pinfunction "WIPER_2") (pintype "passive"))
      (node (ref "U8") (pin "14") (pinfunction "D_14") (pintype "input"))
    )
    (net (code "52") (name "/E1") (class "Default")
      (node (ref "J2") (pin "23") (pinfunction "23_23") (pintype "passive"))
      (node (ref "R22") (pin "2") (pinfunction "WIPER_2") (pintype "passive"))
      (node (ref "U7") (pin "3") (pinfunction "E_3") (pintype "input"))
    )
    (net (code "53") (name "/E2") (class "Default")
      (node (ref "J2") (pin "31") (pinfunction "31_31") (pintype "passive"))
      (node (ref "R30") (pin "2") (pinfunction "WIPER_2") (pintype "passive"))
      (node (ref "U8") (pin "3") (pinfunction "E_3") (pintype "input"))
    )
    (net (code "54") (name "/F1") (class "Default")
      (node (ref "J2") (pin "24") (pinfunction "24_24") (pintype "passive"))
      (node (ref "R23") (pin "2") (pinfunction "WIPER_2") (pintype "passive"))
      (node (ref "U7") (pin "4") (pinfunction "F_4") (pintype "input"))
    )
    (net (code "55") (name "/F2") (class "Default")
      (node (ref "J2") (pin "32") (pinfunction "32_32") (pintype "passive"))
      (node (ref "R31") (pin "2") (pinfunction "WIPER_2") (pintype "passive"))
      (node (ref "U8") (pin "4") (pinfunction "F_4") (pintype "input"))
    )
    (net (code "56") (name "/G1") (class "Default")
      (node (ref "J2") (pin "25") (pinfunction "25_25") (pintype "passive"))
      (node (ref "R24") (pin "2") (pinfunction "WIPER_2") (pintype "passive"))
      (node (ref "U7") (pin "5") (pinfunction "G_5") (pintype "input"))
    )
    (net (code "57") (name "/G2") (class "Default")
      (node (ref "J2") (pin "33") (pinfunction "33_33") (pintype "passive"))
      (node (ref "R32") (pin "2") (pinfunction "WIPER_2") (pintype "passive"))
      (node (ref "U8") (pin "5") (pinfunction "G_5") (pintype "input"))
    )
    (net (code "58") (name "/H1") (class "Default")
      (node (ref "J2") (pin "26") (pinfunction "26_26") (pintype "passive"))
      (node (ref "R25") (pin "2") (pinfunction "WIPER_2") (pintype "passive"))
      (node (ref "U7") (pin "6") (pinfunction "H_6") (pintype "input"))
    )
    (net (code "59") (name "/H2") (class "Default")
      (node (ref "J2") (pin "34") (pinfunction "34_34") (pintype "passive"))
      (node (ref "R33") (pin "2") (pinfunction "WIPER_2") (pintype "passive"))
      (node (ref "U8") (pin "6") (pinfunction "H_6") (pintype "input"))
    )
    (net (code "60") (name "/I2C_CLK") (class "Default")
      (node (ref "P1") (pin "2") (pinfunction "2_2") (pintype "passive"))
      (node (ref "P2") (pin "2") (pinfunction "2_2") (pintype "passive"))
      (node (ref "P3") (pin "2") (pinfunction "2_2") (pintype "passive"))
      (node (ref "P4") (pin "2") (pinfunction "2_2") (pintype "passive"))
      (node (ref "P6") (pin "9") (pinfunction "9_9") (pintype "passive"))
      (node (ref "U1") (pin "9") (pinfunction "D6_9") (pintype "bidirectional"))
    )
    (net (code "61") (name "/I2C_DAT") (class "Default")
      (node (ref "P1") (pin "5") (pinfunction "5_5") (pintype "passive"))
      (node (ref "P2") (pin "5") (pinfunction "5_5") (pintype "passive"))
      (node (ref "P3") (pin "5") (pinfunction "5_5") (pintype "passive"))
      (node (ref "P4") (pin "5") (pinfunction "5_5") (pintype "passive"))
      (node (ref "P6") (pin "8") (pinfunction "8_8") (pintype "passive"))
      (node (ref "U1") (pin "8") (pinfunction "D5_8") (pintype "bidirectional"))
    )
    (net (code "62") (name "/LED_REG_CHAIN1") (class "Default")
      (node (ref "U4") (pin "9") (pinfunction "QH'_9") (pintype "output"))
      (node (ref "U6") (pin "14") (pinfunction "SER_14") (pintype "input"))
    )
    (net (code "63") (name "/LED_REG_CLK") (class "Default")
      (node (ref "P6") (pin "5") (pinfunction "5_5") (pintype "passive"))
      (node (ref "U1") (pin "5") (pinfunction "D2_5") (pintype "bidirectional"))
      (node (ref "U4") (pin "11") (pinfunction "SRCLK_11") (pintype "input"))
      (node (ref "U6") (pin "11") (pinfunction "SRCLK_11") (pintype "input"))
    )
    (net (code "64") (name "/LED_REG_DAT") (class "Default")
      (node (ref "P6") (pin "7") (pinfunction "7_7") (pintype "passive"))
      (node (ref "U1") (pin "7") (pinfunction "D4_7") (pintype "bidirectional"))
      (node (ref "U4") (pin "14") (pinfunction "SER_14") (pintype "input"))
    )
    (net (code "65") (name "/LED_REG_LTCH") (class "Default")
      (node (ref "P6") (pin "6") (pinfunction "6_6") (pintype "passive"))
      (node (ref "U1") (pin "6") (pinfunction "D3_6") (pintype "bidirectional"))
      (node (ref "U4") (pin "12") (pinfunction "RCLK_12") (pintype "input"))
      (node (ref "U6") (pin "12") (pinfunction "RCLK_12") (pintype "input"))
    )
    (net (code "66") (name "/MISO") (class "Default")
      (node (ref "P6") (pin "15") (pinfunction "15_15") (pintype "passive"))
      (node (ref "U1") (pin "15") (pinfunction "D12_15") (pintype "bidirectional"))
      (node (ref "U2") (pin "DO") (pinfunction "DO_DO") (pintype "output"))
    )
    (net (code "67") (name "/MOSI") (class "Default")
      (node (ref "P6") (pin "14") (pinfunction "14_14") (pintype "passive"))
      (node (ref "U1") (pin "14") (pinfunction "D11_14") (pintype "bidirectional"))
      (node (ref "U2") (pin "DI") (pinfunction "DI_DI") (pintype "input"))
    )
    (net (code "68") (name "/R0") (class "Default")
      (node (ref "Q1") (pin "2") (pinfunction "B_2") (pintype "passive"))
      (node (ref "R2") (pin "2") (pinfunction "2_2") (pintype "passive"))
    )
    (net (code "69") (name "/R1") (class "Default")
      (node (ref "Q2") (pin "2") (pinfunction "B_2") (pintype "passive"))
      (node (ref "R3") (pin "2") (pinfunction "2_2") (pintype "passive"))
    )
    (net (code "70") (name "/R2") (class "Default")
      (node (ref "Q3") (pin "2") (pinfunction "B_2") (pintype "passive"))
      (node (ref "R4") (pin "2") (pinfunction "2_2") (pintype "passive"))
    )
    (net (code "71") (name "/R3") (class "Default")
      (node (ref "Q4") (pin "2") (pinfunction "B_2") (pintype "passive"))
      (node (ref "R5") (pin "2") (pinfunction "2_2") (pintype "passive"))
    )
    (net (code "72") (name "/R4") (class "Default")
      (node (ref "Q5") (pin "2") (pinfunction "B_2") (pintype "passive"))
      (node (ref "R6") (pin "2") (pinfunction "2_2") (pintype "passive"))
    )
    (net (code "73") (name "/R5") (class "Default")
      (node (ref "Q6") (pin "2") (pinfunction "B_2") (pintype "passive"))
      (node (ref "R7") (pin "2") (pinfunction "2_2") (pintype "passive"))
    )
    (net (code "74") (name "/R6") (class "Default")
      (node (ref "Q7") (pin "2") (pinfunction "B_2") (pintype "passive"))
      (node (ref "R8") (pin "2") (pinfunction "2_2") (pintype "passive"))
    )
    (net (code "75") (name "/R7") (class "Default")
      (node (ref "Q8") (pin "2") (pinfunction "B_2") (pintype "passive"))
      (node (ref "R9") (pin "2") (pinfunction "2_2") (pintype "passive"))
    )
    (net (code "76") (name "/RESET") (class "Default")
      (node (ref "P6") (pin "3") (pinfunction "3_3") (pintype "passive"))
      (node (ref "SW1") (pin "1") (pinfunction "1_1") (pintype "passive"))
      (node (ref "SW1") (pin "2") (pinfunction "2_2") (pintype "passive"))
      (node (ref "U1") (pin "3") (pinfunction "RESET_1_3") (pintype "input"))
    )
    (net (code "77") (name "/ROW0") (class "Default")
      (node (ref "P9") (pin "1") (pinfunction "1_1") (pintype "passive"))
      (node (ref "Q1") (pin "1") (pinfunction "E_1") (pintype "passive"))
    )
    (net (code "78") (name "/ROW1") (class "Default")
      (node (ref "P9") (pin "2") (pinfunction "2_2") (pintype "passive"))
      (node (ref "Q2") (pin "1") (pinfunction "E_1") (pintype "passive"))
    )
    (net (code "79") (name "/ROW2") (class "Default")
      (node (ref "P9") (pin "3") (pinfunction "3_3") (pintype "passive"))
      (node (ref "Q3") (pin "1") (pinfunction "E_1") (pintype "passive"))
    )
    (net (code "80") (name "/ROW3") (class "Default")
      (node (ref "P9") (pin "4") (pinfunction "4_4") (pintype "passive"))
      (node (ref "Q4") (pin "1") (pinfunction "E_1") (pintype "passive"))
    )
    (net (code "81") (name "/ROW4") (class "Default")
      (node (ref "P9") (pin "5") (pinfunction "5_5") (pintype "passive"))
      (node (ref "Q5") (pin "1") (pinfunction "E_1") (pintype "passive"))
    )
    (net (code "82") (name "/ROW5") (class "Default")
      (node (ref "P9") (pin "6") (pinfunction "6_6") (pintype "passive"))
      (node (ref "Q6") (pin "1") (pinfunction "E_1") (pintype "passive"))
    )
    (net (code "83") (name "/ROW6") (class "Default")
      (node (ref "P9") (pin "7") (pinfunction "7_7") (pintype "passive"))
      (node (ref "Q7") (pin "1") (pinfunction "E_1") (pintype "passive"))
    )
    (net (code "84") (name "/ROW7") (class "Default")
      (node (ref "P9") (pin "8") (pinfunction "8_8") (pintype "passive"))
      (node (ref "Q8") (pin "1") (pinfunction "E_1") (pintype "passive"))
    )
    (net (code "85") (name "/RX") (class "Default")
      (node (ref "J1") (pin "3") (pinfunction "3_3") (pintype "passive"))
      (node (ref "P6") (pin "2") (pinfunction "2_2") (pintype "passive"))
      (node (ref "U1") (pin "2") (pinfunction "D1/RX_2") (pintype "bidirectional"))
    )
    (net (code "86") (name "/SCK") (class "Default")
      (node (ref "P7") (pin "15") (pinfunction "15_15") (pintype "passive"))
      (node (ref "U1") (pin "16") (pinfunction "D13_16") (pintype "bidirectional"))
      (node (ref "U2") (pin "CLK") (pinfunction "CLK_CLK") (pintype "input"))
    )
    (net (code "87") (name "/SENS_REG_CHAIN1") (class "Default")
      (node (ref "U3") (pin "9") (pinfunction "QH'_9") (pintype "output"))
      (node (ref "U5") (pin "14") (pinfunction "SER_14") (pintype "input"))
    )
    (net (code "88") (name "/SENS_ROW0") (class "Default")
      (node (ref "J2") (pin "3") (pinfunction "3_3") (pintype "passive"))
      (node (ref "U3") (pin "15") (pinfunction "QA_15") (pintype "output"))
    )
    (net (code "89") (name "/SENS_ROW1") (class "Default")
      (node (ref "J2") (pin "4") (pinfunction "4_4") (pintype "passive"))
      (node (ref "U3") (pin "1") (pinfunction "QB_1") (pintype "output"))
    )
    (net (code "90") (name "/SENS_ROW2") (class "Default")
      (node (ref "J2") (pin "5") (pinfunction "5_5") (pintype "passive"))
      (node (ref "U3") (pin "2") (pinfunction "QC_2") (pintype "output"))
    )
    (net (code "91") (name "/SENS_ROW3") (class "Default")
      (node (ref "J2") (pin "6") (pinfunction "6_6") (pintype "passive"))
      (node (ref "U3") (pin "3") (pinfunction "QD_3") (pintype "output"))
    )
    (net (code "92") (name "/SENS_ROW4") (class "Default")
      (node (ref "J2") (pin "7") (pinfunction "7_7") (pintype "passive"))
      (node (ref "U3") (pin "4") (pinfunction "QE_4") (pintype "output"))
    )
    (net (code "93") (name "/SENS_ROW5") (class "Default")
      (node (ref "J2") (pin "8") (pinfunction "8_8") (pintype "passive"))
      (node (ref "U3") (pin "5") (pinfunction "QF_5") (pintype "output"))
    )
    (net (code "94") (name "/SENS_ROW6") (class "Default")
      (node (ref "J2") (pin "9") (pinfunction "9_9") (pintype "passive"))
      (node (ref "U3") (pin "6") (pinfunction "QG_6") (pintype "output"))
    )
    (net (code "95") (name "/SENS_ROW7") (class "Default")
      (node (ref "J2") (pin "10") (pinfunction "10_10") (pintype "passive"))
      (node (ref "U3") (pin "7") (pinfunction "QH_7") (pintype "output"))
    )
    (net (code "96") (name "/SENS_ROW8") (class "Default")
      (node (ref "J2") (pin "11") (pinfunction "11_11") (pintype "passive"))
      (node (ref "U5") (pin "15") (pinfunction "QA_15") (pintype "output"))
    )
    (net (code "97") (name "/SENS_ROW9") (class "Default")
      (node (ref "J2") (pin "12") (pinfunction "12_12") (pintype "passive"))
      (node (ref "U5") (pin "1") (pinfunction "QB_1") (pintype "output"))
    )
    (net (code "98") (name "/SENS_ROW10") (class "Default")
      (node (ref "J2") (pin "13") (pinfunction "13_13") (pintype "passive"))
      (node (ref "U5") (pin "2") (pinfunction "QC_2") (pintype "output"))
    )
    (net (code "99") (name "/SENS_ROW11") (class "Default")
      (node (ref "J2") (pin "14") (pinfunction "14_14") (pintype "passive"))
      (node (ref "U5") (pin "3") (pinfunction "QD_3") (pintype "output"))
    )
    (net (code "100") (name "/SENS_ROW12") (class "Default")
      (node (ref "J2") (pin "15") (pinfunction "15_15") (pintype "passive"))
      (node (ref "U5") (pin "4") (pinfunction "QE_4") (pintype "output"))
    )
    (net (code "101") (name "/SENS_ROW13") (class "Default")
      (node (ref "J2") (pin "16") (pinfunction "16_16") (pintype "passive"))
      (node (ref "U5") (pin "5") (pinfunction "QF_5") (pintype "output"))
    )
    (net (code "102") (name "/SENS_ROW14") (class "Default")
      (node (ref "J2") (pin "17") (pinfunction "17_17") (pintype "passive"))
      (node (ref "U5") (pin "6") (pinfunction "QG_6") (pintype "output"))
    )
    (net (code "103") (name "/SENS_ROW15") (class "Default")
      (node (ref "J2") (pin "18") (pinfunction "18_18") (pintype "passive"))
      (node (ref "U5") (pin "7") (pinfunction "QH_7") (pintype "output"))
    )
    (net (code "104") (name "/SENS_ROW_CLK") (class "Default")
      (node (ref "P7") (pin "10") (pinfunction "10_10") (pintype "passive"))
      (node (ref "U1") (pin "21") (pinfunction "A2_21") (pintype "input"))
      (node (ref "U3") (pin "11") (pinfunction "SRCLK_11") (pintype "input"))
      (node (ref "U5") (pin "11") (pinfunction "SRCLK_11") (pintype "input"))
    )
    (net (code "105") (name "/SENS_ROW_DAT") (class "Default")
      (node (ref "P7") (pin "11") (pinfunction "11_11") (pintype "passive"))
      (node (ref "U1") (pin "20") (pinfunction "A1_20") (pintype "input"))
      (node (ref "U3") (pin "14") (pinfunction "SER_14") (pintype "input"))
    )
    (net (code "106") (name "/SENS_ROW_LTCH") (class "Default")
      (node (ref "P7") (pin "12") (pinfunction "12_12") (pintype "passive"))
      (node (ref "U1") (pin "19") (pinfunction "A0_19") (pintype "input"))
      (node (ref "U3") (pin "12") (pinfunction "RCLK_12") (pintype "input"))
      (node (ref "U5") (pin "12") (pinfunction "RCLK_12") (pintype "input"))
    )
    (net (code "107") (name "/SEN_C1") (class "Default")
      (node (ref "J2") (pin "21") (pinfunction "21_21") (pintype "passive"))
      (node (ref "R20") (pin "2") (pinfunction "WIPER_2") (pintype "passive"))
      (node (ref "U7") (pin "13") (pinfunction "C_13") (pintype "input"))
    )
    (net (code "108") (name "/SEN_C2") (class "Default")
      (node (ref "J2") (pin "29") (pinfunction "29_29") (pintype "passive"))
      (node (ref "R28") (pin "2") (pinfunction "WIPER_2") (pintype "passive"))
      (node (ref "U8") (pin "13") (pinfunction "C_13") (pintype "input"))
    )
    (net (code "109") (name "/SNR_REG_CHAIN") (class "Default")
      (node (ref "U7") (pin "10") (pinfunction "SER_10") (pintype "input"))
      (node (ref "U8") (pin "9") (pinfunction "QH_9") (pintype "output"))
    )
    (net (code "110") (name "/SNR_REG_CLK") (class "Default")
      (node (ref "P6") (pin "11") (pinfunction "11_11") (pintype "passive"))
      (node (ref "U1") (pin "11") (pinfunction "D8_11") (pintype "bidirectional"))
      (node (ref "U7") (pin "2") (pinfunction "CLK_2") (pintype "input"))
      (node (ref "U8") (pin "2") (pinfunction "CLK_2") (pintype "input"))
    )
    (net (code "111") (name "/SNR_REG_LOAD") (class "Default")
      (node (ref "P6") (pin "10") (pinfunction "10_10") (pintype "passive"))
      (node (ref "U1") (pin "10") (pinfunction "D7_10") (pintype "bidirectional"))
      (node (ref "U7") (pin "1") (pinfunction "SH/~LD_1") (pintype "input"))
      (node (ref "U8") (pin "1") (pinfunction "SH/~LD_1") (pintype "input"))
    )
    (net (code "112") (name "/SNR_REG_SER_OUT") (class "Default")
      (node (ref "P6") (pin "12") (pinfunction "12_12") (pintype "passive"))
      (node (ref "U1") (pin "12") (pinfunction "D9_12") (pintype "bidirectional"))
      (node (ref "U7") (pin "9") (pinfunction "QH_9") (pintype "output"))
    )
    (net (code "113") (name "/TX") (class "Default")
      (node (ref "J1") (pin "2") (pinfunction "2_2") (pintype "passive"))
      (node (ref "P6") (pin "1") (pinfunction "1_1") (pintype "passive"))
      (node (ref "U1") (pin "1") (pinfunction "D0/TX_1") (pintype "bidirectional"))
    )
    (net (code "114") (name "/Vin") (class "Default")
      (node (ref "J2") (pin "1") (pinfunction "1_1") (pintype "passive"))
      (node (ref "P5") (pin "1") (pinfunction "1_1") (pintype "passive"))
    )
    (net (code "115") (name "GND") (class "Default")
      (node (ref "C1") (pin "2") (pinfunction "2_2") (pintype "passive"))
      (node (ref "C2") (pin "2") (pinfunction "2_2") (pintype "passive"))
      (node (ref "C3") (pin "2") (pinfunction "2_2") (pintype "passive"))
      (node (ref "C4") (pin "2") (pinfunction "2_2") (pintype "passive"))
      (node (ref "C5") (pin "2") (pinfunction "2_2") (pintype "passive"))
      (node (ref "C6") (pin "2") (pinfunction "2_2") (pintype "passive"))
      (node (ref "J1") (pin "4") (pinfunction "4_4") (pintype "passive"))
      (node (ref "P1") (pin "3") (pinfunction "3_3") (pintype "passive"))
      (node (ref "P1") (pin "4") (pinfunction "4_4") (pintype "passive"))
      (node (ref "P2") (pin "3") (pinfunction "3_3") (pintype "passive"))
      (node (ref "P2") (pin "4") (pinfunction "4_4") (pintype "passive"))
      (node (ref "P3") (pin "3") (pinfunction "3_3") (pintype "passive"))
      (node (ref "P3") (pin "4") (pinfunction "4_4") (pintype "passive"))
      (node (ref "P4") (pin "3") (pinfunction "3_3") (pintype "passive"))
      (node (ref "P4") (pin "4") (pinfunction "4_4") (pintype "passive"))
      (node (ref "P5") (pin "5") (pinfunction "5_5") (pintype "passive"))
      (node (ref "P6") (pin "4") (pinfunction "4_4") (pintype "passive"))
      (node (ref "P7") (pin "2") (pinfunction "2_2") (pintype "passive"))
      (node (ref "P8") (pin "2") (pinfunction "2_2") (pintype "passive"))
      (node (ref "P8") (pin "4") (pinfunction "4_4") (pintype "passive"))
      (node (ref "Q10") (pin "1") (pinfunction "E_1") (pintype "passive"))
      (node (ref "Q11") (pin "1") (pinfunction "E_1") (pintype "passive"))
      (node (ref "Q12") (pin "1") (pinfunction "E_1") (pintype "passive"))
      (node (ref "Q13") (pin "1") (pinfunction "E_1") (pintype "passive"))
      (node (ref "Q14") (pin "1") (pinfunction "E_1") (pintype "passive"))
      (node (ref "Q15") (pin "1") (pinfunction "E_1") (pintype "passive"))
      (node (ref "Q16") (pin "1") (pinfunction "E_1") (pintype "passive"))
      (node (ref "Q9") (pin "1") (pinfunction "E_1") (pintype "passive"))
      (node (ref "R1") (pin "1") (pinfunction "1_1") (pintype "passive"))
      (node (ref "R18") (pin "1") (pinfunction "CCW_1") (pintype "passive"))
      (node (ref "R19") (pin "1") (pinfunction "CCW_1") (pintype "passive"))
      (node (ref "R20") (pin "1") (pinfunction "CCW_1") (pintype "passive"))
      (node (ref "R21") (pin "1") (pinfunction "CCW_1") (pintype "passive"))
      (node (ref "R22") (pin "1") (pinfunction "CCW_1") (pintype "passive"))
      (node (ref "R23") (pin "1") (pinfunction "CCW_1") (pintype "passive"))
      (node (ref "R24") (pin "1") (pinfunction "CCW_1") (pintype "passive"))
      (node (ref "R25") (pin "1") (pinfunction "CCW_1") (pintype "passive"))
      (node (ref "R26") (pin "1") (pinfunction "CCW_1") (pintype "passive"))
      (node (ref "R27") (pin "1") (pinfunction "CCW_1") (pintype "passive"))
      (node (ref "R28") (pin "1") (pinfunction "CCW_1") (pintype "passive"))
      (node (ref "R29") (pin "1") (pinfunction "CCW_1") (pintype "passive"))
      (node (ref "R30") (pin "1") (pinfunction "CCW_1") (pintype "passive"))
      (node (ref "R31") (pin "1") (pinfunction "CCW_1") (pintype "passive"))
      (node (ref "R32") (pin "1") (pinfunction "CCW_1") (pintype "passive"))
      (node (ref "R33") (pin "1") (pinfunction "CCW_1") (pintype "passive"))
      (node (ref "SW1") (pin "3") (pinfunction "3_3") (pintype "passive"))
      (node (ref "SW1") (pin "4") (pinfunction "4_4") (pintype "passive"))
      (node (ref "U1") (pin "29") (pinfunction "GND_2_29") (pintype "power_in"))
      (node (ref "U1") (pin "4") (pinfunction "GND_1_4") (pintype "power_in"))
      (node (ref "U2") (pin "GND") (pinfunction "GND_GND") (pintype "power_in"))
      (node (ref "U3") (pin "13") (pinfunction "OE_13") (pintype "input"))
      (node (ref "U3") (pin "8") (pinfunction "GND_8") (pintype "power_in"))
      (node (ref "U4") (pin "13") (pinfunction "OE_13") (pintype "input"))
      (node (ref "U4") (pin "8") (pinfunction "GND_8") (pintype "power_in"))
      (node (ref "U5") (pin "13") (pinfunction "OE_13") (pintype "input"))
      (node (ref "U5") (pin "8") (pinfunction "GND_8") (pintype "power_in"))
      (node (ref "U6") (pin "13") (pinfunction "OE_13") (pintype "input"))
      (node (ref "U6") (pin "8") (pinfunction "GND_8") (pintype "power_in"))
      (node (ref "U7") (pin "15") (pinfunction "CLK_INH_15") (pintype "input"))
      (node (ref "U7") (pin "8") (pinfunction "GND_8") (pintype "power_in"))
      (node (ref "U8") (pin "10") (pinfunction "SER_10") (pintype "input"))
      (node (ref "U8") (pin "15") (pinfunction "CLK_INH_15") (pintype "input"))
      (node (ref "U8") (pin "8") (pinfunction "GND_8") (pintype "power_in"))
    )
    (net (code "116") (name "Net-(D1-A)") (class "Default")
      (node (ref "D1") (pin "1") (pinfunction "A_1") (pintype "passive"))
      (node (ref "R1") (pin "2") (pinfunction "2_2") (pintype "passive"))
    )
    (net (code "117") (name "Net-(D2-A)") (class "Default")
      (node (ref "D2") (pin "1") (pinfunction "A_1") (pintype "passive"))
      (node (ref "Q19") (pin "2") (pinfunction "G_2") (pintype "passive"))
      (node (ref "R35") (pin "2") (pinfunction "2_2") (pintype "passive"))
    )
    (net (code "118") (name "Net-(Q18-G)") (class "Default")
      (node (ref "Q18") (pin "2") (pinfunction "G_2") (pintype "passive"))
      (node (ref "Q19") (pin "3") (pinfunction "S_3") (pintype "passive"))
      (node (ref "R34") (pin "2") (pinfunction "2_2") (pintype "passive"))
    )
    (net (code "119") (name "VCC") (class "Default")
      (node (ref "C1") (pin "1") (pinfunction "1_1") (pintype "passive"))
      (node (ref "C2") (pin "1") (pinfunction "1_1") (pintype "passive"))
      (node (ref "C3") (pin "1") (pinfunction "1_1") (pintype "passive"))
      (node (ref "C4") (pin "1") (pinfunction "1_1") (pintype "passive"))
      (node (ref "C5") (pin "1") (pinfunction "1_1") (pintype "passive"))
      (node (ref "C6") (pin "1") (pinfunction "1_1") (pintype "passive"))
      (node (ref "D1") (pin "2") (pinfunction "K_2") (pintype "passive"))
      (node (ref "J1") (pin "5") (pinfunction "5_5") (pintype "passive"))
      (node (ref "P1") (pin "1") (pinfunction "1_1") (pintype "passive"))
      (node (ref "P1") (pin "6") (pinfunction "6_6") (pintype "passive"))
      (node (ref "P2") (pin "1") (pinfunction "1_1") (pintype "passive"))
      (node (ref "P2") (pin "6") (pinfunction "6_6") (pintype "passive"))
      (node (ref "P3") (pin "1") (pinfunction "1_1") (pintype "passive"))
      (node (ref "P3") (pin "6") (pinfunction "6_6") (pintype "passive"))
      (node (ref "P4") (pin "1") (pinfunction "1_1") (pintype "passive"))
      (node (ref "P4") (pin "6") (pinfunction "6_6") (pintype "passive"))
      (node (ref "P5") (pin "6") (pinfunction "6_6") (pintype "passive"))
      (node (ref "P7") (pin "1") (pinfunction "1_1") (pintype "passive"))
      (node (ref "P8") (pin "1") (pinfunction "1_1") (pintype "passive"))
      (node (ref "P8") (pin "3") (pinfunction "3_3") (pintype "passive"))
      (node (ref "Q1") (pin "3") (pinfunction "C_3") (pintype "passive"))
      (node (ref "Q2") (pin "3") (pinfunction "C_3") (pintype "passive"))
      (node (ref "Q3") (pin "3") (pinfunction "C_3") (pintype "passive"))
      (node (ref "Q4") (pin "3") (pinfunction "C_3") (pintype "passive"))
      (node (ref "Q5") (pin "3") (pinfunction "C_3") (pintype "passive"))
      (node (ref "Q6") (pin "3") (pinfunction "C_3") (pintype "passive"))
      (node (ref "Q7") (pin "3") (pinfunction "C_3") (pintype "passive"))
      (node (ref "Q8") (pin "3") (pinfunction "C_3") (pintype "passive"))
      (node (ref "U1") (pin "30") (pinfunction "VIN_30") (pintype "power_in"))
      (node (ref "U2") (pin "5V") (pinfunction "5V_5V") (pintype "power_in"))
      (node (ref "U3") (pin "10") (pinfunction "SRCLR_10") (pintype "input"))
      (node (ref "U3") (pin "16") (pinfunction "VCC_16") (pintype "power_in"))
      (node (ref "U4") (pin "10") (pinfunction "SRCLR_10") (pintype "input"))
      (node (ref "U4") (pin "16") (pinfunction "VCC_16") (pintype "power_in"))
      (node (ref "U5") (pin "10") (pinfunction "SRCLR_10") (pintype "input"))
      (node (ref "U5") (pin "16") (pinfunction "VCC_16") (pintype "power_in"))
      (node (ref "U6") (pin "10") (pinfunction "SRCLR_10") (pintype "input"))
      (node (ref "U6") (pin "16") (pinfunction "VCC_16") (pintype "power_in"))
      (node (ref "U7") (pin "16") (pinfunction "VCC_16") (pintype "power_in"))
      (node (ref "U8") (pin "16") (pinfunction "VCC_16") (pintype "power_in"))
    )
    (net (code "120") (name "unconnected-(J1-Pad1)") (class "Default")
      (node (ref "J1") (pin "1") (pinfunction "1_1") (pintype "passive"))
    )
    (net (code "121") (name "unconnected-(J1-Pad6)") (class "Default")
      (node (ref "J1") (pin "6") (pinfunction "6_6") (pintype "passive"))
    )
    (net (code "122") (name "unconnected-(Q17-B-Pad2)") (class "Default")
      (node (ref "Q17") (pin "2") (pinfunction "B_2") (pintype "passive"))
    )
    (net (code "123") (name "unconnected-(Q17-C-Pad1)") (class "Default")
      (node (ref "Q17") (pin "1") (pinfunction "C_1") (pintype "passive"))
    )
    (net (code "124") (name "unconnected-(Q17-E-Pad3)") (class "Default")
      (node (ref "Q17") (pin "3") (pinfunction "E_3") (pintype "passive"))
    )
    (net (code "125") (name "unconnected-(R18-CW-Pad3)") (class "Default")
      (node (ref "R18") (pin "3") (pinfunction "CW_3") (pintype "passive"))
    )
    (net (code "126") (name "unconnected-(R19-CW-Pad3)") (class "Default")
      (node (ref "R19") (pin "3") (pinfunction "CW_3") (pintype "passive"))
    )
    (net (code "127") (name "unconnected-(R20-CW-Pad3)") (class "Default")
      (node (ref "R20") (pin "3") (pinfunction "CW_3") (pintype "passive"))
    )
    (net (code "128") (name "unconnected-(R21-CW-Pad3)") (class "Default")
      (node (ref "R21") (pin "3") (pinfunction "CW_3") (pintype "passive"))
    )
    (net (code "129") (name "unconnected-(R22-CW-Pad3)") (class "Default")
      (node (ref "R22") (pin "3") (pinfunction "CW_3") (pintype "passive"))
    )
    (net (code "130") (name "unconnected-(R23-CW-Pad3)") (class "Default")
      (node (ref "R23") (pin "3") (pinfunction "CW_3") (pintype "passive"))
    )
    (net (code "131") (name "unconnected-(R24-CW-Pad3)") (class "Default")
      (node (ref "R24") (pin "3") (pinfunction "CW_3") (pintype "passive"))
    )
    (net (code "132") (name "unconnected-(R25-CW-Pad3)") (class "Default")
      (node (ref "R25") (pin "3") (pinfunction "CW_3") (pintype "passive"))
    )
    (net (code "133") (name "unconnected-(R26-CW-Pad3)") (class "Default")
      (node (ref "R26") (pin "3") (pinfunction "CW_3") (pintype "passive"))
    )
    (net (code "134") (name "unconnected-(R27-CW-Pad3)") (class "Default")
      (node (ref "R27") (pin "3") (pinfunction "CW_3") (pintype "passive"))
    )
    (net (code "135") (name "unconnected-(R28-CW-Pad3)") (class "Default")
      (node (ref "R28") (pin "3") (pinfunction "CW_3") (pintype "passive"))
    )
    (net (code "136") (name "unconnected-(R29-CW-Pad3)") (class "Default")
      (node (ref "R29") (pin "3") (pinfunction "CW_3") (pintype "passive"))
    )
    (net (code "137") (name "unconnected-(R30-CW-Pad3)") (class "Default")
      (node (ref "R30") (pin "3") (pinfunction "CW_3") (pintype "passive"))
    )
    (net (code "138") (name "unconnected-(R31-CW-Pad3)") (class "Default")
      (node (ref "R31") (pin "3") (pinfunction "CW_3") (pintype "passive"))
    )
    (net (code "139") (name "unconnected-(R32-CW-Pad3)") (class "Default")
      (node (ref "R32") (pin "3") (pinfunction "CW_3") (pintype "passive"))
    )
    (net (code "140") (name "unconnected-(R33-CW-Pad3)") (class "Default")
      (node (ref "R33") (pin "3") (pinfunction "CW_3") (pintype "passive"))
    )
    (net (code "141") (name "unconnected-(U2-Pad3V)") (class "Default")
      (node (ref "U2") (pin "3V") (pinfunction "3V_3V") (pintype "power_in"))
    )
    (net (code "142") (name "unconnected-(U2-PadCD)") (class "Default")
      (node (ref "U2") (pin "CD") (pinfunction "CD_CD") (pintype "bidirectional"))
    )
    (net (code "143") (name "unconnected-(U5-QH'-Pad9)") (class "Default")
      (node (ref "U5") (pin "9") (pinfunction "QH'_9") (pintype "output"))
    )
    (net (code "144") (name "unconnected-(U6-QH'-Pad9)") (class "Default")
      (node (ref "U6") (pin "9") (pinfunction "QH'_9") (pintype "output"))
    )
    (net (code "145") (name "unconnected-(U7-~{QH}-Pad7)") (class "Default")
      (node (ref "U7") (pin "7") (pinfunction "~{QH}_7") (pintype "output"))
    )
    (net (code "146") (name "unconnected-(U8-~{QH}-Pad7)") (class "Default")
      (node (ref "U8") (pin "7") (pinfunction "~{QH}_7") (pintype "output"))
    )
  )
)
